# staj1.net
KiCad netlist of a schematic drawn in EAGLE
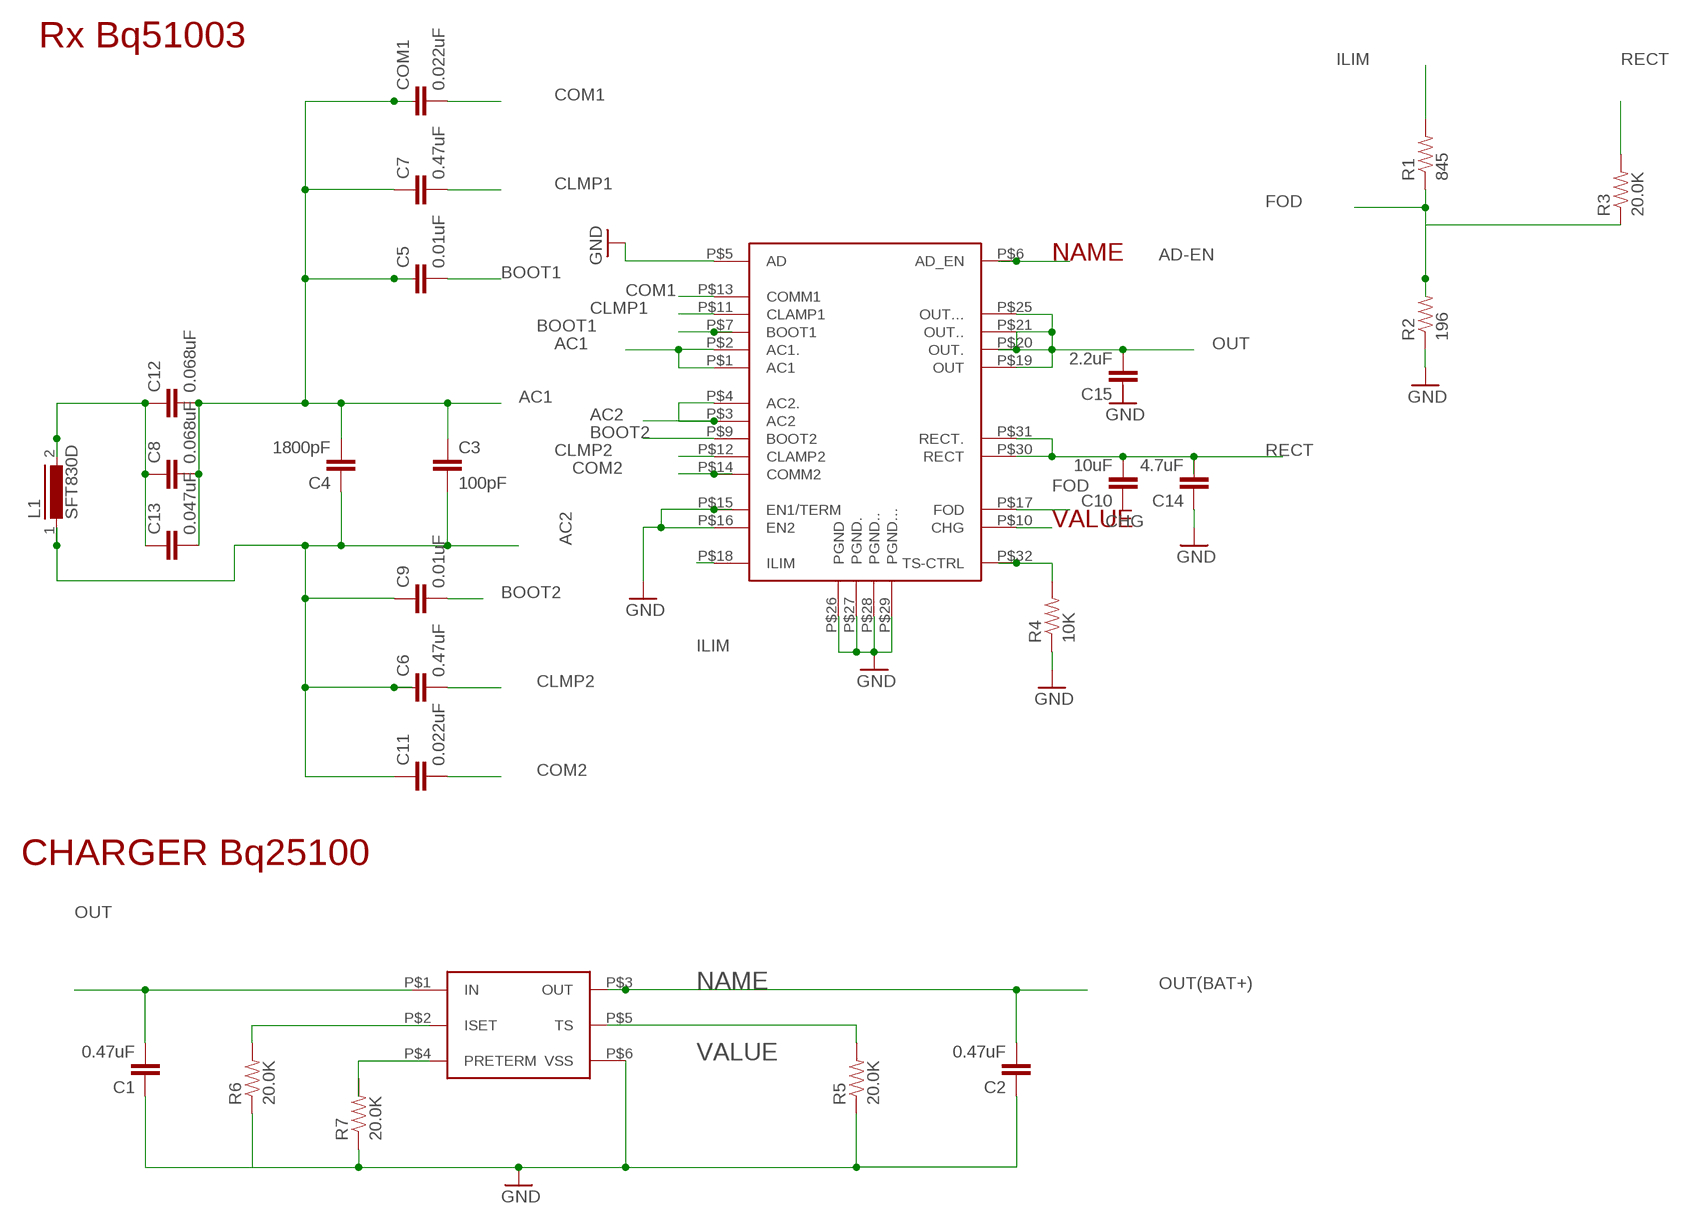
[diagram p0: schematic, sheet 1]

(export (version "E")
  (design (tool "Eeschema 10.0.6"))
  (components
    (comp (ref "C1")
      (value "0.47uF")
      (footprint "eagle-import:0603-CAP")
      (libsource (lib "eagle-import") (part "0.1UF-25V(+80/-20%)(0603)"))
    )
    (comp (ref "C2")
      (value "0.47uF")
      (footprint "eagle-import:0603-CAP")
      (libsource (lib "eagle-import") (part "0.1UF-25V(+80/-20%)(0603)"))
    )
    (comp (ref "C3")
      (value "100pF")
      (footprint "eagle-import:0603-CAP")
      (libsource (lib "eagle-import") (part "0.1UF-25V(+80/-20%)(0603)"))
    )
    (comp (ref "C4")
      (value "1800pF")
      (footprint "eagle-import:0603-CAP")
      (libsource (lib "eagle-import") (part "0.1UF-25V(+80/-20%)(0603)"))
    )
    (comp (ref "C5")
      (value "0.01uF")
      (footprint "eagle-import:0603-CAP")
      (libsource (lib "eagle-import") (part "0.1UF-25V(+80/-20%)(0603)"))
    )
    (comp (ref "C6")
      (value "0.47uF")
      (footprint "eagle-import:0603-CAP")
      (libsource (lib "eagle-import") (part "0.1UF-25V(+80/-20%)(0603)"))
    )
    (comp (ref "C7")
      (value "0.47uF")
      (footprint "eagle-import:0603-CAP")
      (libsource (lib "eagle-import") (part "0.1UF-25V(+80/-20%)(0603)"))
    )
    (comp (ref "C8")
      (value "0.068uF")
      (footprint "eagle-import:0603-CAP")
      (libsource (lib "eagle-import") (part "0.1UF-25V(+80/-20%)(0603)"))
    )
    (comp (ref "C9")
      (value "0.01uF")
      (footprint "eagle-import:0603-CAP")
      (libsource (lib "eagle-import") (part "0.1UF-25V(+80/-20%)(0603)"))
    )
    (comp (ref "C10")
      (value "10uF")
      (footprint "eagle-import:0603-CAP")
      (libsource (lib "eagle-import") (part "0.1UF-25V(+80/-20%)(0603)"))
    )
    (comp (ref "C11")
      (value "0.022uF")
      (footprint "eagle-import:0603-CAP")
      (libsource (lib "eagle-import") (part "0.1UF-25V(+80/-20%)(0603)"))
    )
    (comp (ref "C12")
      (value "0.068uF")
      (footprint "eagle-import:0603-CAP")
      (libsource (lib "eagle-import") (part "0.1UF-25V(+80/-20%)(0603)"))
    )
    (comp (ref "C13")
      (value "0.047uF")
      (footprint "eagle-import:0603-CAP")
      (libsource (lib "eagle-import") (part "0.1UF-25V(+80/-20%)(0603)"))
    )
    (comp (ref "C14")
      (value "4.7uF")
      (footprint "eagle-import:0603-CAP")
      (libsource (lib "eagle-import") (part "0.1UF-25V(+80/-20%)(0603)"))
    )
    (comp (ref "C15")
      (value "2.2uF")
      (footprint "eagle-import:0603-CAP")
      (libsource (lib "eagle-import") (part "0.1UF-25V(+80/-20%)(0603)"))
    )
    (comp (ref "COM1")
      (value "0.022uF")
      (footprint "eagle-import:0603-CAP")
      (libsource (lib "eagle-import") (part "0.1UF-25V(+80/-20%)(0603)"))
    )
    (comp (ref "L1")
      (value "SFT830D")
      (footprint "eagle-import:SFT830D")
      (libsource (lib "eagle-import") (part "SFT830D"))
    )
    (comp (ref "R1")
      (value "845")
      (footprint "eagle-import:0603-RES")
      (libsource (lib "eagle-import") (part "10KOHM-1/10W-1%(0603)0603"))
    )
    (comp (ref "R2")
      (value "196")
      (footprint "eagle-import:0603-RES")
      (libsource (lib "eagle-import") (part "10KOHM-1/10W-1%(0603)0603"))
    )
    (comp (ref "R3")
      (value "20.0K")
      (footprint "eagle-import:0603-RES")
      (libsource (lib "eagle-import") (part "10KOHM-1/10W-1%(0603)0603"))
    )
    (comp (ref "R4")
      (value "10K")
      (footprint "eagle-import:0603-RES")
      (libsource (lib "eagle-import") (part "10KOHM-1/10W-1%(0603)0603"))
    )
    (comp (ref "R5")
      (value "20.0K")
      (footprint "eagle-import:0603-RES")
      (libsource (lib "eagle-import") (part "10KOHM-1/10W-1%(0603)0603"))
    )
    (comp (ref "R6")
      (value "20.0K")
      (footprint "eagle-import:0603-RES")
      (libsource (lib "eagle-import") (part "10KOHM-1/10W-1%(0603)0603"))
    )
    (comp (ref "R7")
      (value "20.0K")
      (footprint "eagle-import:0603-RES")
      (libsource (lib "eagle-import") (part "10KOHM-1/10W-1%(0603)0603"))
    )
    (comp (ref "U$1")
      (value "BQ51003")
      (footprint "eagle-import:BQ51003")
      (libsource (lib "eagle-import") (part "BQ51003"))
    )
    (comp (ref "U$2")
      (value "BQ25100")
      (footprint "eagle-import:BQ25100")
      (libsource (lib "eagle-import") (part "BQ25100"))
    )
  )
  (nets
    (net (code "1") (name "/AC1") (class "Default")
      (node (ref "C12") (pin "2") (pinfunction "2_2") (pintype "passive"))
      (node (ref "C13") (pin "2") (pinfunction "2_2") (pintype "passive"))
      (node (ref "C3") (pin "1") (pinfunction "1_1") (pintype "passive"))
      (node (ref "C4") (pin "2") (pinfunction "2_2") (pintype "passive"))
      (node (ref "C5") (pin "1") (pinfunction "1_1") (pintype "passive"))
      (node (ref "C7") (pin "1") (pinfunction "1_1") (pintype "passive"))
      (node (ref "C8") (pin "2") (pinfunction "2_2") (pintype "passive"))
      (node (ref "COM1") (pin "1") (pinfunction "1_1") (pintype "passive"))
      (node (ref "U$1") (pin "P$1") (pinfunction "AC1_P$1") (pintype "bidirectional"))
      (node (ref "U$1") (pin "P$2") (pinfunction "AC1._P$2") (pintype "bidirectional"))
    )
    (net (code "2") (name "/AC2") (class "Default")
      (node (ref "C11") (pin "1") (pinfunction "1_1") (pintype "passive"))
      (node (ref "C3") (pin "2") (pinfunction "2_2") (pintype "passive"))
      (node (ref "C4") (pin "1") (pinfunction "1_1") (pintype "passive"))
      (node (ref "C6") (pin "1") (pinfunction "1_1") (pintype "passive"))
      (node (ref "C9") (pin "1") (pinfunction "1_1") (pintype "passive"))
      (node (ref "L1") (pin "1") (pinfunction "1_1") (pintype "passive"))
      (node (ref "U$1") (pin "P$3") (pinfunction "AC2_P$3") (pintype "bidirectional"))
      (node (ref "U$1") (pin "P$4") (pinfunction "AC2._P$4") (pintype "bidirectional"))
    )
    (net (code "3") (name "/AD-EN") (class "Default")
      (node (ref "U$1") (pin "P$6") (pinfunction "AD_EN_P$6") (pintype "bidirectional"))
    )
    (net (code "4") (name "/BOOT1") (class "Default")
      (node (ref "C5") (pin "2") (pinfunction "2_2") (pintype "passive"))
      (node (ref "U$1") (pin "P$7") (pinfunction "BOOT1_P$7") (pintype "bidirectional"))
    )
    (net (code "5") (name "/BOOT2") (class "Default")
      (node (ref "C9") (pin "2") (pinfunction "2_2") (pintype "passive"))
      (node (ref "U$1") (pin "P$9") (pinfunction "BOOT2_P$9") (pintype "bidirectional"))
    )
    (net (code "6") (name "/CHG") (class "Default")
      (node (ref "U$1") (pin "P$10") (pinfunction "CHG_P$10") (pintype "bidirectional"))
    )
    (net (code "7") (name "/CLMP1") (class "Default")
      (node (ref "C7") (pin "2") (pinfunction "2_2") (pintype "passive"))
      (node (ref "U$1") (pin "P$11") (pinfunction "CLAMP1_P$11") (pintype "bidirectional"))
    )
    (net (code "8") (name "/CLMP2") (class "Default")
      (node (ref "C6") (pin "2") (pinfunction "2_2") (pintype "passive"))
      (node (ref "U$1") (pin "P$12") (pinfunction "CLAMP2_P$12") (pintype "bidirectional"))
    )
    (net (code "9") (name "/COM1") (class "Default")
      (node (ref "COM1") (pin "2") (pinfunction "2_2") (pintype "passive"))
      (node (ref "U$1") (pin "P$13") (pinfunction "COMM1_P$13") (pintype "bidirectional"))
    )
    (net (code "10") (name "/COM2") (class "Default")
      (node (ref "C11") (pin "2") (pinfunction "2_2") (pintype "passive"))
      (node (ref "U$1") (pin "P$14") (pinfunction "COMM2_P$14") (pintype "bidirectional"))
    )
    (net (code "11") (name "/FOD") (class "Default")
      (node (ref "R1") (pin "1") (pinfunction "1_1") (pintype "passive"))
      (node (ref "R2") (pin "2") (pinfunction "2_2") (pintype "passive"))
      (node (ref "R3") (pin "1") (pinfunction "1_1") (pintype "passive"))
      (node (ref "U$1") (pin "P$17") (pinfunction "FOD_P$17") (pintype "bidirectional"))
    )
    (net (code "12") (name "/ILIM") (class "Default")
      (node (ref "R1") (pin "2") (pinfunction "2_2") (pintype "passive"))
      (node (ref "U$1") (pin "P$18") (pinfunction "ILIM_P$18") (pintype "bidirectional"))
    )
    (net (code "13") (name "/OUT") (class "Default")
      (node (ref "C1") (pin "2") (pinfunction "2_2") (pintype "passive"))
      (node (ref "C15") (pin "2") (pinfunction "2_2") (pintype "passive"))
      (node (ref "U$1") (pin "P$19") (pinfunction "OUT_P$19") (pintype "bidirectional"))
      (node (ref "U$1") (pin "P$20") (pinfunction "OUT._P$20") (pintype "bidirectional"))
      (node (ref "U$1") (pin "P$21") (pinfunction "OUT.._P$21") (pintype "bidirectional"))
      (node (ref "U$1") (pin "P$25") (pinfunction "OUT..._P$25") (pintype "bidirectional"))
      (node (ref "U$2") (pin "P$1") (pinfunction "IN_P$1") (pintype "bidirectional"))
    )
    (net (code "14") (name "/OUT(BAT+)") (class "Default")
      (node (ref "C2") (pin "2") (pinfunction "2_2") (pintype "passive"))
      (node (ref "U$2") (pin "P$3") (pinfunction "OUT_P$3") (pintype "bidirectional"))
    )
    (net (code "15") (name "/RECT") (class "Default")
      (node (ref "C10") (pin "2") (pinfunction "2_2") (pintype "passive"))
      (node (ref "C14") (pin "2") (pinfunction "2_2") (pintype "passive"))
      (node (ref "R3") (pin "2") (pinfunction "2_2") (pintype "passive"))
      (node (ref "U$1") (pin "P$30") (pinfunction "RECT_P$30") (pintype "bidirectional"))
      (node (ref "U$1") (pin "P$31") (pinfunction "RECT._P$31") (pintype "bidirectional"))
    )
    (net (code "16") (name "GND") (class "Default")
      (node (ref "C1") (pin "1") (pinfunction "1_1") (pintype "passive"))
      (node (ref "C14") (pin "1") (pinfunction "1_1") (pintype "passive"))
      (node (ref "C2") (pin "1") (pinfunction "1_1") (pintype "passive"))
      (node (ref "R2") (pin "1") (pinfunction "1_1") (pintype "passive"))
      (node (ref "R4") (pin "1") (pinfunction "1_1") (pintype "passive"))
      (node (ref "R5") (pin "1") (pinfunction "1_1") (pintype "passive"))
      (node (ref "R6") (pin "1") (pinfunction "1_1") (pintype "passive"))
      (node (ref "R7") (pin "1") (pinfunction "1_1") (pintype "passive"))
      (node (ref "U$1") (pin "P$15") (pinfunction "EN1/TERM_P$15") (pintype "bidirectional"))
      (node (ref "U$1") (pin "P$16") (pinfunction "EN2_P$16") (pintype "bidirectional"))
      (node (ref "U$1") (pin "P$26") (pinfunction "PGND_P$26") (pintype "bidirectional"))
      (node (ref "U$1") (pin "P$27") (pinfunction "PGND._P$27") (pintype "bidirectional"))
      (node (ref "U$1") (pin "P$28") (pinfunction "PGND.._P$28") (pintype "bidirectional"))
      (node (ref "U$1") (pin "P$29") (pinfunction "PGND..._P$29") (pintype "bidirectional"))
      (node (ref "U$1") (pin "P$5") (pinfunction "AD_P$5") (pintype "open_collector"))
      (node (ref "U$2") (pin "P$6") (pinfunction "VSS_P$6") (pintype "bidirectional"))
    )
    (net (code "17") (name "Net-(C12-Pad1)") (class "Default")
      (node (ref "C12") (pin "1") (pinfunction "1_1") (pintype "passive"))
      (node (ref "C13") (pin "1") (pinfunction "1_1") (pintype "passive"))
      (node (ref "C8") (pin "1") (pinfunction "1_1") (pintype "passive"))
      (node (ref "L1") (pin "2") (pinfunction "2_2") (pintype "passive"))
    )
    (net (code "18") (name "Net-(U$1-TS-CTRL)") (class "Default")
      (node (ref "R4") (pin "2") (pinfunction "2_2") (pintype "passive"))
      (node (ref "U$1") (pin "P$32") (pinfunction "TS-CTRL_P$32") (pintype "bidirectional"))
    )
    (net (code "19") (name "unconnected-(C10-Pad1)") (class "Default")
      (node (ref "C10") (pin "1") (pinfunction "1_1") (pintype "passive"))
    )
    (net (code "20") (name "unconnected-(C15-Pad1)") (class "Default")
      (node (ref "C15") (pin "1") (pinfunction "1_1") (pintype "passive"))
    )
    (net (code "21") (name "unconnected-(R5-Pad2)") (class "Default")
      (node (ref "R5") (pin "2") (pinfunction "2_2") (pintype "passive"))
    )
    (net (code "22") (name "unconnected-(R6-Pad2)") (class "Default")
      (node (ref "R6") (pin "2") (pinfunction "2_2") (pintype "passive"))
    )
    (net (code "23") (name "unconnected-(R7-Pad2)") (class "Default")
      (node (ref "R7") (pin "2") (pinfunction "2_2") (pintype "passive"))
    )
    (net (code "24") (name "unconnected-(U$2-ISET-PadP$2)") (class "Default")
      (node (ref "U$2") (pin "P$2") (pinfunction "ISET_P$2") (pintype "bidirectional"))
    )
    (net (code "25") (name "unconnected-(U$2-PRETERM-PadP$4)") (class "Default")
      (node (ref "U$2") (pin "P$4") (pinfunction "PRETERM_P$4") (pintype "bidirectional"))
    )
    (net (code "26") (name "unconnected-(U$2-TS-PadP$5)") (class "Default")
      (node (ref "U$2") (pin "P$5") (pinfunction "TS_P$5") (pintype "bidirectional"))
    )
  )
)
